# UART_Driver.net
KiCad netlist of a schematic drawn in Altium Designer
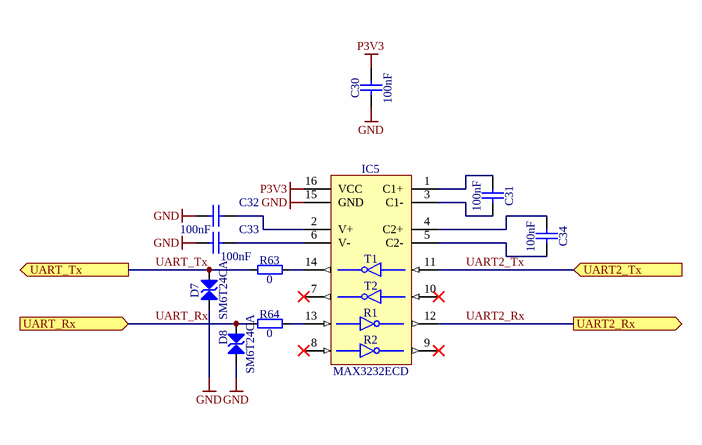
[diagram p0: UART_Driver.SchDoc]

(export (version "E")
  (design (tool "Eeschema 10.0.6"))
  (components
    (comp (ref "C30")
      (value "100nF")
      (footprint "CAPC1608X87N")
      (description "Non-polarised capacitor")
      (fields
        (field (name "PART NUMBER") "CC0603_100NF_50V_10%_X7R")
        (field (name "VOLTAGE") "50V")
        (field (name "AUTHOR") "CERN DEM JLC")
      )
      (libsource (lib "Capacitors") (part "Capacitor - non polarized"))
    )
    (comp (ref "C31")
      (value "100nF")
      (footprint "CAPC1608X87N")
      (description "Non-polarised capacitor")
      (fields
        (field (name "PART NUMBER") "CC0603_100NF_50V_10%_X7R")
        (field (name "VOLTAGE") "50V")
        (field (name "AUTHOR") "CERN DEM JLC")
      )
      (libsource (lib "Capacitors") (part "Capacitor - non polarized"))
    )
    (comp (ref "C32")
      (value "100nF")
      (footprint "CAPC1608X87N")
      (description "Non-polarised capacitor")
      (fields
        (field (name "PART NUMBER") "CC0603_100NF_50V_10%_X7R")
        (field (name "VOLTAGE") "50V")
        (field (name "AUTHOR") "CERN DEM JLC")
      )
      (libsource (lib "Capacitors") (part "Capacitor - non polarized"))
    )
    (comp (ref "C33")
      (value "100nF")
      (footprint "CAPC1608X87N")
      (description "Non-polarised capacitor")
      (fields
        (field (name "PART NUMBER") "CC0603_100NF_50V_10%_X7R")
        (field (name "VOLTAGE") "50V")
        (field (name "AUTHOR") "CERN DEM JLC")
      )
      (libsource (lib "Capacitors") (part "Capacitor - non polarized"))
    )
    (comp (ref "C34")
      (value "100nF")
      (footprint "CAPC1608X87N")
      (description "Non-polarised capacitor")
      (fields
        (field (name "PART NUMBER") "CC0603_100NF_50V_10%_X7R")
        (field (name "VOLTAGE") "50V")
        (field (name "AUTHOR") "CERN DEM JLC")
      )
      (libsource (lib "Capacitors") (part "Capacitor - non polarized"))
    )
    (comp (ref "D7")
      (value "SM6T24CA")
      (footprint "DIOM5436X265N")
      (description "Transient Voltage Suppressor Diode (Bi-Directional)")
      (fields
        (field (name "VOLTAGE") "24V")
        (field (name "POWER") "600W")
        (field (name "AUTHOR") "CERN DEM JMW")
      )
      (libsource (lib "ICs And Semiconductors") (part "Diode TVS Bi-Directional"))
    )
    (comp (ref "D8")
      (value "SM6T24CA")
      (footprint "DIOM5436X265N")
      (description "Transient Voltage Suppressor Diode (Bi-Directional)")
      (fields
        (field (name "VOLTAGE") "24V")
        (field (name "POWER") "600W")
        (field (name "AUTHOR") "CERN DEM JMW")
      )
      (libsource (lib "ICs And Semiconductors") (part "Diode TVS Bi-Directional"))
    )
    (comp (ref "IC5")
      (value "MAX3232ECD")
      (footprint "SOIC127P600X175-16N")
      (description "3-V To 5.5-V Multichannel RS-232 Line Driver/Receiver With ±15kV IEC ESD Protection")
      (fields (field (name "MANUFACTURER") "TEXAS INSTRUMENTS") (field (name "AUTHOR") "CERN DEM JLC"))
      (libsource (lib "ICs And Semiconductors") (part "MAX3232ECD"))
    )
    (comp (ref "R63")
      (value "0")
      (footprint "RESC1608X55N")
      (description "Resistor")
      (fields
        (field (name "PART NUMBER") "R0603_0R_JUMPER")
        (field (name "MANUFACTURER") "GENERIC")
        (field (name "AUTHOR") "CERN DEM JLC")
      )
      (libsource (lib "Resistors") (part "Resistor"))
    )
    (comp (ref "R64")
      (value "0")
      (footprint "RESC1608X55N")
      (description "Resistor")
      (fields
        (field (name "PART NUMBER") "R0603_0R_JUMPER")
        (field (name "MANUFACTURER") "GENERIC")
        (field (name "AUTHOR") "CERN DEM JLC")
      )
      (libsource (lib "Resistors") (part "Resistor"))
    )
  )
  (nets
    (net (code "1") (name "/UART2_Rx") (class "Default")
      (node (ref "IC5") (pin "12") (pinfunction "R1OUT_12") (pintype "output"))
    )
    (net (code "2") (name "/UART2_Tx") (class "Default")
      (node (ref "IC5") (pin "11") (pinfunction "T1IN_11") (pintype "input"))
    )
    (net (code "3") (name "/UART_Rx") (class "Default")
      (node (ref "D8") (pin "1") (pinfunction "C_1") (pintype "passive"))
      (node (ref "R64") (pin "1") (pinfunction "1_1") (pintype "passive"))
    )
    (net (code "4") (name "/UART_Tx") (class "Default")
      (node (ref "D7") (pin "1") (pinfunction "C_1") (pintype "passive"))
      (node (ref "R63") (pin "1") (pinfunction "1_1") (pintype "passive"))
    )
    (net (code "5") (name "GND") (class "Default")
      (node (ref "C30") (pin "1") (pinfunction "1_1") (pintype "passive"))
      (node (ref "C32") (pin "2") (pinfunction "2_2") (pintype "passive"))
      (node (ref "C33") (pin "2") (pinfunction "2_2") (pintype "passive"))
      (node (ref "D7") (pin "2") (pinfunction "A_2") (pintype "passive"))
      (node (ref "D8") (pin "2") (pinfunction "A_2") (pintype "passive"))
      (node (ref "IC5") (pin "15") (pinfunction "GND_15") (pintype "power_in"))
    )
    (net (code "6") (name "Net-(IC5-C1+)") (class "Default")
      (node (ref "C31") (pin "2") (pinfunction "2_2") (pintype "passive"))
      (node (ref "IC5") (pin "1") (pinfunction "C1+_1") (pintype "passive"))
    )
    (net (code "7") (name "Net-(IC5-C1-)") (class "Default")
      (node (ref "C31") (pin "1") (pinfunction "1_1") (pintype "passive"))
      (node (ref "IC5") (pin "3") (pinfunction "C1-_3") (pintype "passive"))
    )
    (net (code "8") (name "Net-(IC5-C2+)") (class "Default")
      (node (ref "C34") (pin "2") (pinfunction "2_2") (pintype "passive"))
      (node (ref "IC5") (pin "4") (pinfunction "C2+_4") (pintype "passive"))
    )
    (net (code "9") (name "Net-(IC5-C2-)") (class "Default")
      (node (ref "C34") (pin "1") (pinfunction "1_1") (pintype "passive"))
      (node (ref "IC5") (pin "5") (pinfunction "C2-_5") (pintype "passive"))
    )
    (net (code "10") (name "Net-(IC5-R1IN)") (class "Default")
      (node (ref "IC5") (pin "13") (pinfunction "R1IN_13") (pintype "input"))
      (node (ref "R64") (pin "2") (pinfunction "2_2") (pintype "passive"))
    )
    (net (code "11") (name "Net-(IC5-T1OUT)") (class "Default")
      (node (ref "IC5") (pin "14") (pinfunction "T1OUT_14") (pintype "output"))
      (node (ref "R63") (pin "2") (pinfunction "2_2") (pintype "passive"))
    )
    (net (code "12") (name "Net-(IC5-V+)") (class "Default")
      (node (ref "C32") (pin "1") (pinfunction "1_1") (pintype "passive"))
      (node (ref "IC5") (pin "2") (pinfunction "V+_2") (pintype "power_in"))
    )
    (net (code "13") (name "Net-(IC5-V-)") (class "Default")
      (node (ref "C33") (pin "1") (pinfunction "1_1") (pintype "passive"))
      (node (ref "IC5") (pin "6") (pinfunction "V-_6") (pintype "power_in"))
    )
    (net (code "14") (name "P3V3") (class "Default")
      (node (ref "C30") (pin "2") (pinfunction "2_2") (pintype "passive"))
      (node (ref "IC5") (pin "16") (pinfunction "VCC_16") (pintype "power_in"))
    )
    (net (code "15") (name "unconnected-(IC5-R2IN-Pad8)") (class "Default")
      (node (ref "IC5") (pin "8") (pinfunction "R2IN_8") (pintype "input+no_connect"))
    )
    (net (code "16") (name "unconnected-(IC5-R2OUT-Pad9)") (class "Default")
      (node (ref "IC5") (pin "9") (pinfunction "R2OUT_9") (pintype "output+no_connect"))
    )
    (net (code "17") (name "unconnected-(IC5-T2IN-Pad10)") (class "Default")
      (node (ref "IC5") (pin "10") (pinfunction "T2IN_10") (pintype "input+no_connect"))
    )
    (net (code "18") (name "unconnected-(IC5-T2OUT-Pad7)") (class "Default")
      (node (ref "IC5") (pin "7") (pinfunction "T2OUT_7") (pintype "output+no_connect"))
    )
  )
)
